# M302D.net
KiCad netlist of a schematic drawn in EAGLE
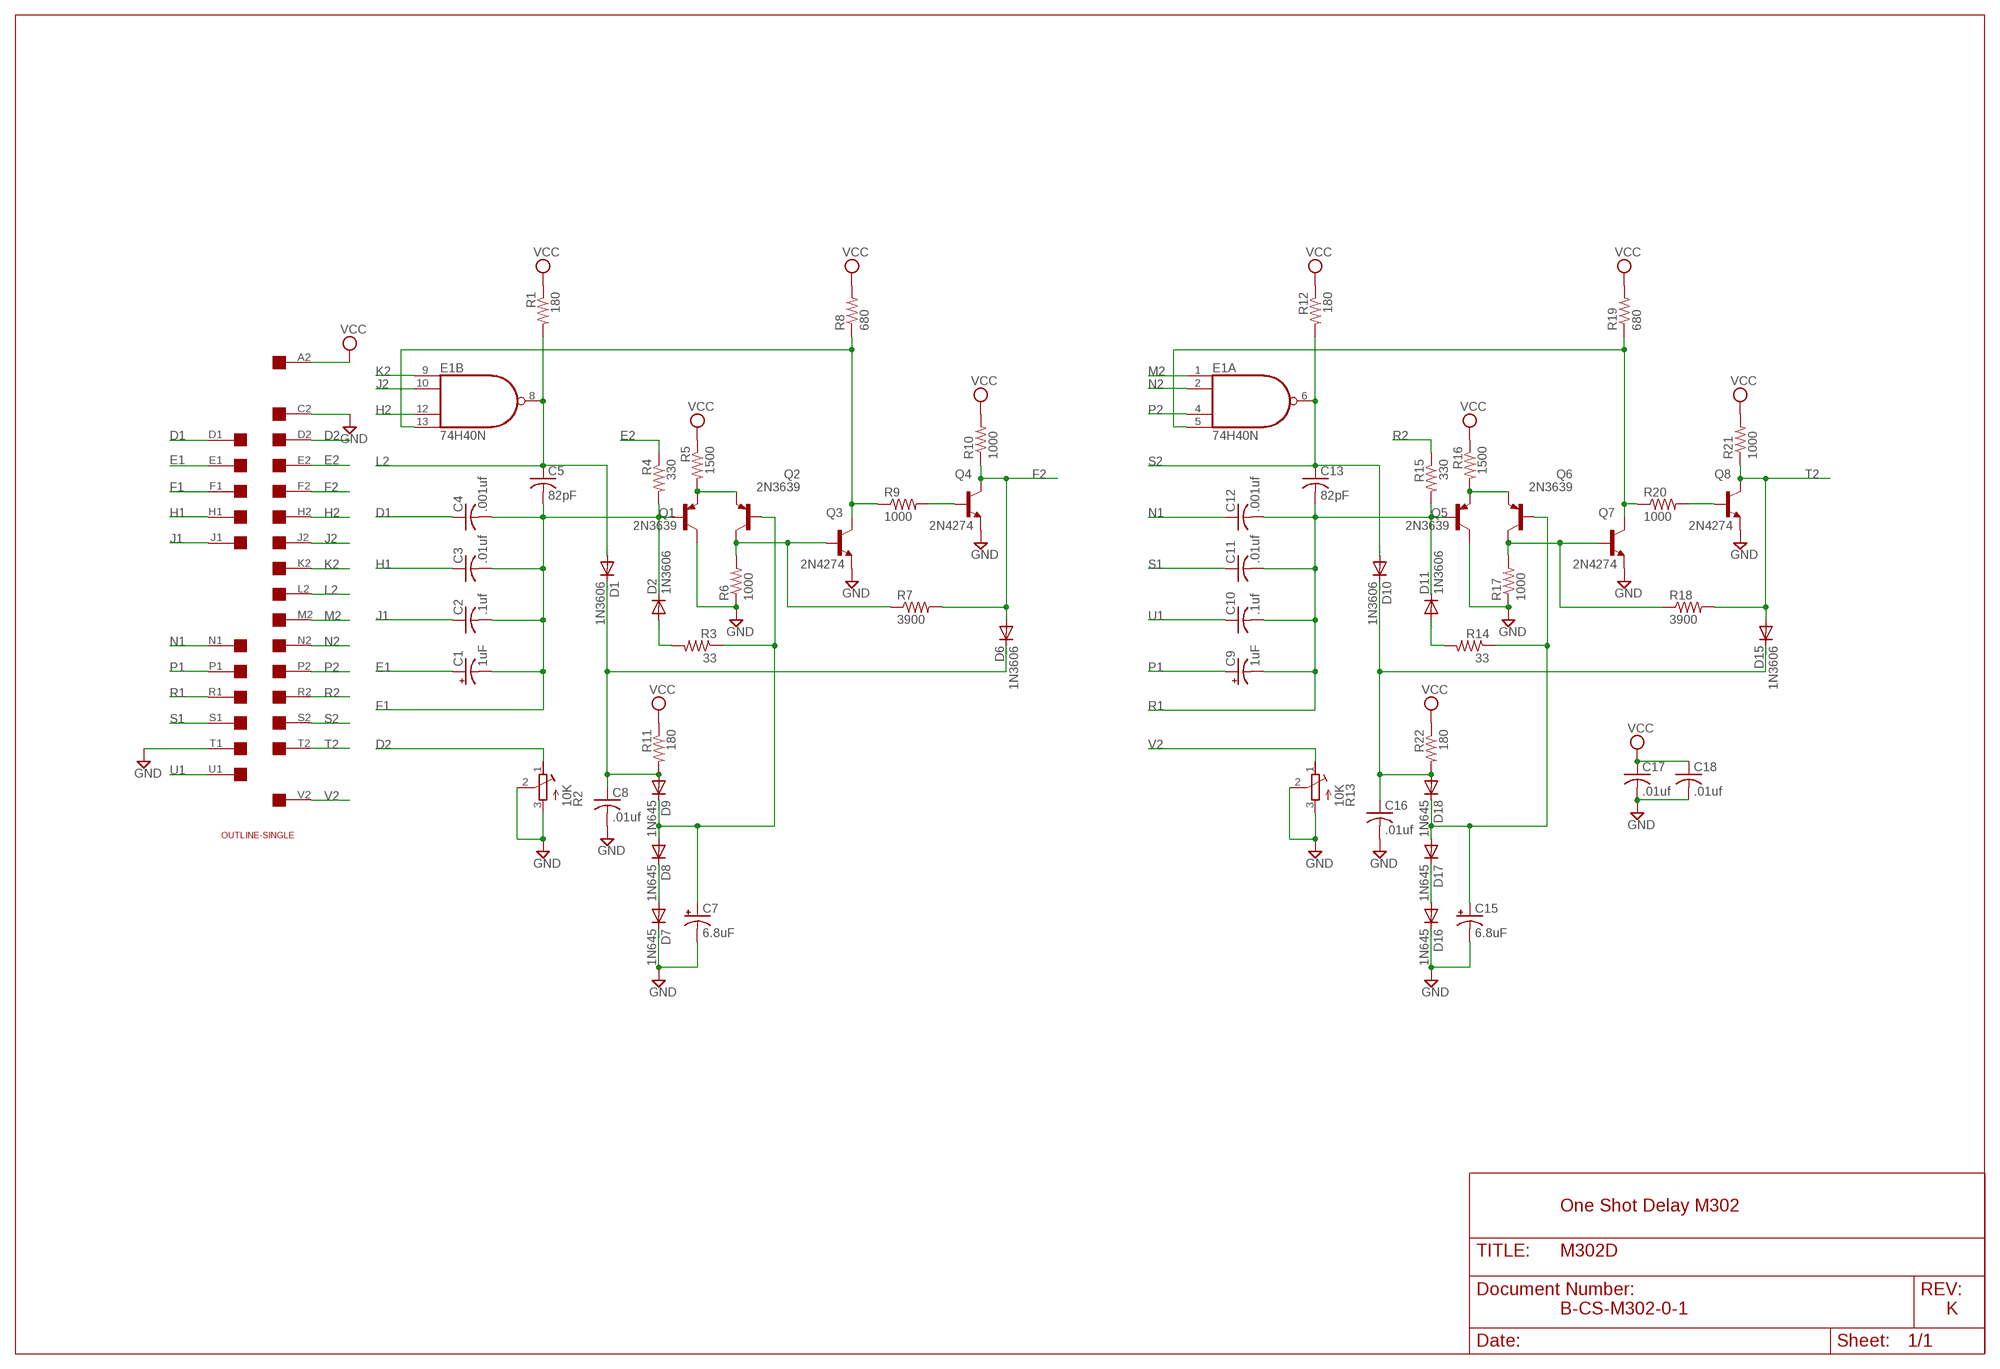
[diagram p0: schematic, sheet 1]

(export (version "E")
  (design (tool "Eeschema 10.0.6"))
  (components
    (comp (ref "C1")
      (value "1uF")
      (footprint "eagle-import:E12-4")
      (libsource (lib "eagle-import") (part "CPOL-USE12-4AXIAL"))
    )
    (comp (ref "C2")
      (value ".1uf")
      (footprint "eagle-import:C275-093X316")
      (libsource (lib "eagle-import") (part "C-US275-093X316"))
    )
    (comp (ref "C3")
      (value ".01uf")
      (footprint "eagle-import:C225-062X268")
      (libsource (lib "eagle-import") (part "C-US225-062X268"))
    )
    (comp (ref "C4")
      (value ".001uf")
      (footprint "eagle-import:C150-054X183")
      (libsource (lib "eagle-import") (part "C-US150-054X183"))
    )
    (comp (ref "C5")
      (value "82pF")
      (footprint "eagle-import:C075-032X103")
      (libsource (lib "eagle-import") (part "C-US075-032X103"))
    )
    (comp (ref "C7")
      (value "6.8uF")
      (footprint "eagle-import:E15-5")
      (libsource (lib "eagle-import") (part "CPOL-USE15-5AXIAL"))
    )
    (comp (ref "C8")
      (value ".01uf")
      (footprint "eagle-import:C050-025X075")
      (libsource (lib "eagle-import") (part "C-US050-025X075"))
    )
    (comp (ref "C9")
      (value "1uF")
      (footprint "eagle-import:E12-4")
      (libsource (lib "eagle-import") (part "CPOL-USE12-4AXIAL"))
    )
    (comp (ref "C10")
      (value ".1uf")
      (footprint "eagle-import:C275-093X316")
      (libsource (lib "eagle-import") (part "C-US275-093X316"))
    )
    (comp (ref "C11")
      (value ".01uf")
      (footprint "eagle-import:C225-062X268")
      (libsource (lib "eagle-import") (part "C-US225-062X268"))
    )
    (comp (ref "C12")
      (value ".001uf")
      (footprint "eagle-import:C150-054X183")
      (libsource (lib "eagle-import") (part "C-US150-054X183"))
    )
    (comp (ref "C13")
      (value "82pF")
      (footprint "eagle-import:C075-032X103")
      (libsource (lib "eagle-import") (part "C-US075-032X103"))
    )
    (comp (ref "C15")
      (value "6.8uF")
      (footprint "eagle-import:E15-5")
      (libsource (lib "eagle-import") (part "CPOL-USE15-5AXIAL"))
    )
    (comp (ref "C16")
      (value ".01uf")
      (footprint "eagle-import:C050-025X075")
      (libsource (lib "eagle-import") (part "C-US050-025X075"))
    )
    (comp (ref "C17")
      (value ".01uf")
      (footprint "eagle-import:C050-025X075")
      (libsource (lib "eagle-import") (part "C-US050-025X075"))
    )
    (comp (ref "C18")
      (value ".01uf")
      (footprint "eagle-import:C050-025X075")
      (libsource (lib "eagle-import") (part "C-US050-025X075"))
    )
    (comp (ref "D1")
      (value "1N3606")
      (footprint "eagle-import:DO35-10")
      (libsource (lib "eagle-import") (part "1N4148DO35-10"))
    )
    (comp (ref "D2")
      (value "1N3606")
      (footprint "eagle-import:DO35-10")
      (libsource (lib "eagle-import") (part "1N4148DO35-10"))
    )
    (comp (ref "D6")
      (value "1N3606")
      (footprint "eagle-import:DO35-10")
      (libsource (lib "eagle-import") (part "1N4148DO35-10"))
    )
    (comp (ref "D7")
      (value "1N645")
      (footprint "eagle-import:DO35-10")
      (libsource (lib "eagle-import") (part "1N4148DO35-10"))
    )
    (comp (ref "D8")
      (value "1N645")
      (footprint "eagle-import:DO35-10")
      (libsource (lib "eagle-import") (part "1N4148DO35-10"))
    )
    (comp (ref "D9")
      (value "1N645")
      (footprint "eagle-import:DO35-10")
      (libsource (lib "eagle-import") (part "1N4148DO35-10"))
    )
    (comp (ref "D10")
      (value "1N3606")
      (footprint "eagle-import:DO35-10")
      (libsource (lib "eagle-import") (part "1N4148DO35-10"))
    )
    (comp (ref "D11")
      (value "1N3606")
      (footprint "eagle-import:DO35-10")
      (libsource (lib "eagle-import") (part "1N4148DO35-10"))
    )
    (comp (ref "D15")
      (value "1N3606")
      (footprint "eagle-import:DO35-10")
      (libsource (lib "eagle-import") (part "1N4148DO35-10"))
    )
    (comp (ref "D16")
      (value "1N645")
      (footprint "eagle-import:DO35-10")
      (libsource (lib "eagle-import") (part "1N4148DO35-10"))
    )
    (comp (ref "D17")
      (value "1N645")
      (footprint "eagle-import:DO35-10")
      (libsource (lib "eagle-import") (part "1N4148DO35-10"))
    )
    (comp (ref "D18")
      (value "1N645")
      (footprint "eagle-import:DO35-10")
      (libsource (lib "eagle-import") (part "1N4148DO35-10"))
    )
    (comp (ref "E1")
      (value "74H40N")
      (footprint "eagle-import:DIL14")
      (libsource (lib "eagle-import") (part "7420NS"))
    )
    (comp (ref "Q1")
      (value "2N3639")
      (footprint "eagle-import:TO39")
      (libsource (lib "eagle-import") (part "-PNP-TO39-EBC2N3637"))
    )
    (comp (ref "Q2")
      (value "2N3639")
      (footprint "eagle-import:TO39")
      (libsource (lib "eagle-import") (part "-PNP-TO39-EBC2N3637"))
    )
    (comp (ref "Q3")
      (value "2N4274")
      (footprint "eagle-import:TO39")
      (libsource (lib "eagle-import") (part "-NPN-TO39-EBC2N3019"))
    )
    (comp (ref "Q4")
      (value "2N4274")
      (footprint "eagle-import:TO39")
      (libsource (lib "eagle-import") (part "-NPN-TO39-EBC2N3019"))
    )
    (comp (ref "Q5")
      (value "2N3639")
      (footprint "eagle-import:TO39")
      (libsource (lib "eagle-import") (part "-PNP-TO39-EBC2N3637"))
    )
    (comp (ref "Q6")
      (value "2N3639")
      (footprint "eagle-import:TO39")
      (libsource (lib "eagle-import") (part "-PNP-TO39-EBC2N3637"))
    )
    (comp (ref "Q7")
      (value "2N4274")
      (footprint "eagle-import:TO39")
      (libsource (lib "eagle-import") (part "-NPN-TO39-EBC2N3019"))
    )
    (comp (ref "Q8")
      (value "2N4274")
      (footprint "eagle-import:TO39")
      (libsource (lib "eagle-import") (part "-NPN-TO39-EBC2N3019"))
    )
    (comp (ref "R1")
      (value "180")
      (footprint "eagle-import:0207_10")
      (libsource (lib "eagle-import") (part "R-US_0207/10"))
    )
    (comp (ref "R2")
      (value "10K")
      (footprint "eagle-import:3006Y")
      (libsource (lib "eagle-import") (part "275P"))
    )
    (comp (ref "R3")
      (value "33")
      (footprint "eagle-import:0207_10")
      (libsource (lib "eagle-import") (part "R-US_0207/10"))
    )
    (comp (ref "R4")
      (value "330")
      (footprint "eagle-import:0207_10")
      (libsource (lib "eagle-import") (part "R-US_0207/10"))
    )
    (comp (ref "R5")
      (value "1500")
      (footprint "eagle-import:0207_10")
      (libsource (lib "eagle-import") (part "R-US_0207/10"))
    )
    (comp (ref "R6")
      (value "1000")
      (footprint "eagle-import:0207_10")
      (libsource (lib "eagle-import") (part "R-US_0207/10"))
    )
    (comp (ref "R7")
      (value "3900")
      (footprint "eagle-import:0207_10")
      (libsource (lib "eagle-import") (part "R-US_0207/10"))
    )
    (comp (ref "R8")
      (value "680")
      (footprint "eagle-import:0207_10")
      (libsource (lib "eagle-import") (part "R-US_0207/10"))
    )
    (comp (ref "R9")
      (value "1000")
      (footprint "eagle-import:0207_10")
      (libsource (lib "eagle-import") (part "R-US_0207/10"))
    )
    (comp (ref "R10")
      (value "1000")
      (footprint "eagle-import:0207_10")
      (libsource (lib "eagle-import") (part "R-US_0207/10"))
    )
    (comp (ref "R11")
      (value "180")
      (footprint "eagle-import:0207_10")
      (libsource (lib "eagle-import") (part "R-US_0207/10"))
    )
    (comp (ref "R12")
      (value "180")
      (footprint "eagle-import:0207_10")
      (libsource (lib "eagle-import") (part "R-US_0207/10"))
    )
    (comp (ref "R13")
      (value "10K")
      (footprint "eagle-import:3006Y")
      (libsource (lib "eagle-import") (part "275P"))
    )
    (comp (ref "R14")
      (value "33")
      (footprint "eagle-import:0207_10")
      (libsource (lib "eagle-import") (part "R-US_0207/10"))
    )
    (comp (ref "R15")
      (value "330")
      (footprint "eagle-import:0207_10")
      (libsource (lib "eagle-import") (part "R-US_0207/10"))
    )
    (comp (ref "R16")
      (value "1500")
      (footprint "eagle-import:0207_10")
      (libsource (lib "eagle-import") (part "R-US_0207/10"))
    )
    (comp (ref "R17")
      (value "1000")
      (footprint "eagle-import:0207_10")
      (libsource (lib "eagle-import") (part "R-US_0207/10"))
    )
    (comp (ref "R18")
      (value "3900")
      (footprint "eagle-import:0207_10")
      (libsource (lib "eagle-import") (part "R-US_0207/10"))
    )
    (comp (ref "R19")
      (value "680")
      (footprint "eagle-import:0207_10")
      (libsource (lib "eagle-import") (part "R-US_0207/10"))
    )
    (comp (ref "R20")
      (value "1000")
      (footprint "eagle-import:0207_10")
      (libsource (lib "eagle-import") (part "R-US_0207/10"))
    )
    (comp (ref "R21")
      (value "1000")
      (footprint "eagle-import:0207_10")
      (libsource (lib "eagle-import") (part "R-US_0207/10"))
    )
    (comp (ref "R22")
      (value "180")
      (footprint "eagle-import:0207_10")
      (libsource (lib "eagle-import") (part "R-US_0207/10"))
    )
    (comp (ref "U$1")
      (value "SINGLE")
      (footprint "eagle-import:EDGE-CON2")
      (libsource (lib "eagle-import") (part "SINGLE"))
    )
    (comp (ref "U$2")
      (value "OUTLINE-SINGLE")
      (footprint "eagle-import:SINGLE")
      (libsource (lib "eagle-import") (part "OUTLINE-SINGLE"))
    )
  )
  (nets
    (net (code "1") (name "/D1") (class "Default")
      (node (ref "C4") (pin "1") (pinfunction "1_1") (pintype "passive"))
      (node (ref "U$1") (pin "D1") (pinfunction "1_D1") (pintype "bidirectional"))
    )
    (net (code "2") (name "/D2") (class "Default")
      (node (ref "R2") (pin "1") (pinfunction "A_1") (pintype "passive"))
      (node (ref "U$1") (pin "D2") (pinfunction "1_D2") (pintype "bidirectional"))
    )
    (net (code "3") (name "/E1") (class "Default")
      (node (ref "C1") (pin "+") (pinfunction "+_+") (pintype "passive"))
      (node (ref "U$1") (pin "E1") (pinfunction "1_E1") (pintype "bidirectional"))
    )
    (net (code "4") (name "/E2") (class "Default")
      (node (ref "R4") (pin "1") (pinfunction "1_1") (pintype "passive"))
      (node (ref "U$1") (pin "E2") (pinfunction "1_E2") (pintype "bidirectional"))
    )
    (net (code "5") (name "/F1") (class "Default")
      (node (ref "C1") (pin "-") (pinfunction "-_-") (pintype "passive"))
      (node (ref "C2") (pin "2") (pinfunction "2_2") (pintype "passive"))
      (node (ref "C3") (pin "2") (pinfunction "2_2") (pintype "passive"))
      (node (ref "C4") (pin "2") (pinfunction "2_2") (pintype "passive"))
      (node (ref "C5") (pin "2") (pinfunction "2_2") (pintype "passive"))
      (node (ref "D2") (pin "C") (pinfunction "C_C") (pintype "passive"))
      (node (ref "Q1") (pin "2") (pinfunction "B_2") (pintype "passive"))
      (node (ref "R4") (pin "2") (pinfunction "2_2") (pintype "passive"))
      (node (ref "U$1") (pin "F1") (pinfunction "1_F1") (pintype "bidirectional"))
    )
    (net (code "6") (name "/F2") (class "Default")
      (node (ref "D6") (pin "A") (pinfunction "A_A") (pintype "passive"))
      (node (ref "Q4") (pin "3") (pinfunction "C_3") (pintype "passive"))
      (node (ref "R10") (pin "1") (pinfunction "1_1") (pintype "passive"))
      (node (ref "R7") (pin "2") (pinfunction "2_2") (pintype "passive"))
      (node (ref "U$1") (pin "F2") (pinfunction "1_F2") (pintype "bidirectional"))
    )
    (net (code "7") (name "/H1") (class "Default")
      (node (ref "C3") (pin "1") (pinfunction "1_1") (pintype "passive"))
      (node (ref "U$1") (pin "H1") (pinfunction "1_H1") (pintype "bidirectional"))
    )
    (net (code "8") (name "/H2") (class "Default")
      (node (ref "E1") (pin "12") (pinfunction "I2_12") (pintype "input"))
      (node (ref "U$1") (pin "H2") (pinfunction "1_H2") (pintype "bidirectional"))
    )
    (net (code "9") (name "/J1") (class "Default")
      (node (ref "C2") (pin "1") (pinfunction "1_1") (pintype "passive"))
      (node (ref "U$1") (pin "J1") (pinfunction "1_J1") (pintype "bidirectional"))
    )
    (net (code "10") (name "/J2") (class "Default")
      (node (ref "E1") (pin "10") (pinfunction "I1_10") (pintype "input"))
      (node (ref "U$1") (pin "J2") (pinfunction "1_J2") (pintype "bidirectional"))
    )
    (net (code "11") (name "/K2") (class "Default")
      (node (ref "E1") (pin "9") (pinfunction "I0_9") (pintype "input"))
      (node (ref "U$1") (pin "K2") (pinfunction "1_K2") (pintype "bidirectional"))
    )
    (net (code "12") (name "/L2") (class "Default")
      (node (ref "C5") (pin "1") (pinfunction "1_1") (pintype "passive"))
      (node (ref "D1") (pin "A") (pinfunction "A_A") (pintype "passive"))
      (node (ref "E1") (pin "8") (pinfunction "O_8") (pintype "output"))
      (node (ref "R1") (pin "2") (pinfunction "2_2") (pintype "passive"))
      (node (ref "U$1") (pin "L2") (pinfunction "1_L2") (pintype "bidirectional"))
    )
    (net (code "13") (name "/M2") (class "Default")
      (node (ref "E1") (pin "1") (pinfunction "I0_1") (pintype "input"))
      (node (ref "U$1") (pin "M2") (pinfunction "1_M2") (pintype "bidirectional"))
    )
    (net (code "14") (name "/N1") (class "Default")
      (node (ref "C12") (pin "1") (pinfunction "1_1") (pintype "passive"))
      (node (ref "U$1") (pin "N1") (pinfunction "1_N1") (pintype "bidirectional"))
    )
    (net (code "15") (name "/N2") (class "Default")
      (node (ref "E1") (pin "2") (pinfunction "I1_2") (pintype "input"))
      (node (ref "U$1") (pin "N2") (pinfunction "1_N2") (pintype "bidirectional"))
    )
    (net (code "16") (name "/P1") (class "Default")
      (node (ref "C9") (pin "+") (pinfunction "+_+") (pintype "passive"))
      (node (ref "U$1") (pin "P1") (pinfunction "1_P1") (pintype "bidirectional"))
    )
    (net (code "17") (name "/P2") (class "Default")
      (node (ref "E1") (pin "4") (pinfunction "I2_4") (pintype "input"))
      (node (ref "U$1") (pin "P2") (pinfunction "1_P2") (pintype "bidirectional"))
    )
    (net (code "18") (name "/R1") (class "Default")
      (node (ref "C10") (pin "2") (pinfunction "2_2") (pintype "passive"))
      (node (ref "C11") (pin "2") (pinfunction "2_2") (pintype "passive"))
      (node (ref "C12") (pin "2") (pinfunction "2_2") (pintype "passive"))
      (node (ref "C13") (pin "2") (pinfunction "2_2") (pintype "passive"))
      (node (ref "C9") (pin "-") (pinfunction "-_-") (pintype "passive"))
      (node (ref "D11") (pin "C") (pinfunction "C_C") (pintype "passive"))
      (node (ref "Q5") (pin "2") (pinfunction "B_2") (pintype "passive"))
      (node (ref "R15") (pin "2") (pinfunction "2_2") (pintype "passive"))
      (node (ref "U$1") (pin "R1") (pinfunction "1_R1") (pintype "bidirectional"))
    )
    (net (code "19") (name "/R2") (class "Default")
      (node (ref "R15") (pin "1") (pinfunction "1_1") (pintype "passive"))
      (node (ref "U$1") (pin "R2") (pinfunction "1_R2") (pintype "bidirectional"))
    )
    (net (code "20") (name "/S1") (class "Default")
      (node (ref "C11") (pin "1") (pinfunction "1_1") (pintype "passive"))
      (node (ref "U$1") (pin "S1") (pinfunction "1_S1") (pintype "bidirectional"))
    )
    (net (code "21") (name "/S2") (class "Default")
      (node (ref "C13") (pin "1") (pinfunction "1_1") (pintype "passive"))
      (node (ref "D10") (pin "A") (pinfunction "A_A") (pintype "passive"))
      (node (ref "E1") (pin "6") (pinfunction "O_6") (pintype "output"))
      (node (ref "R12") (pin "2") (pinfunction "2_2") (pintype "passive"))
      (node (ref "U$1") (pin "S2") (pinfunction "1_S2") (pintype "bidirectional"))
    )
    (net (code "22") (name "/T2") (class "Default")
      (node (ref "D15") (pin "A") (pinfunction "A_A") (pintype "passive"))
      (node (ref "Q8") (pin "3") (pinfunction "C_3") (pintype "passive"))
      (node (ref "R18") (pin "2") (pinfunction "2_2") (pintype "passive"))
      (node (ref "R21") (pin "1") (pinfunction "1_1") (pintype "passive"))
      (node (ref "U$1") (pin "T2") (pinfunction "1_T2") (pintype "bidirectional"))
    )
    (net (code "23") (name "/U1") (class "Default")
      (node (ref "C10") (pin "1") (pinfunction "1_1") (pintype "passive"))
      (node (ref "U$1") (pin "U1") (pinfunction "1_U1") (pintype "bidirectional"))
    )
    (net (code "24") (name "/V2") (class "Default")
      (node (ref "R13") (pin "1") (pinfunction "A_1") (pintype "passive"))
      (node (ref "U$1") (pin "V2") (pinfunction "1_V2") (pintype "bidirectional"))
    )
    (net (code "25") (name "GND") (class "Default")
      (node (ref "C15") (pin "-") (pinfunction "-_-") (pintype "passive"))
      (node (ref "C16") (pin "2") (pinfunction "2_2") (pintype "passive"))
      (node (ref "C17") (pin "2") (pinfunction "2_2") (pintype "passive"))
      (node (ref "C18") (pin "2") (pinfunction "2_2") (pintype "passive"))
      (node (ref "C7") (pin "-") (pinfunction "-_-") (pintype "passive"))
      (node (ref "C8") (pin "2") (pinfunction "2_2") (pintype "passive"))
      (node (ref "D16") (pin "C") (pinfunction "C_C") (pintype "passive"))
      (node (ref "D7") (pin "C") (pinfunction "C_C") (pintype "passive"))
      (node (ref "Q1") (pin "3") (pinfunction "C_3") (pintype "passive"))
      (node (ref "Q3") (pin "1") (pinfunction "E_1") (pintype "passive"))
      (node (ref "Q4") (pin "1") (pinfunction "E_1") (pintype "passive"))
      (node (ref "Q5") (pin "3") (pinfunction "C_3") (pintype "passive"))
      (node (ref "Q7") (pin "1") (pinfunction "E_1") (pintype "passive"))
      (node (ref "Q8") (pin "1") (pinfunction "E_1") (pintype "passive"))
      (node (ref "R13") (pin "2") (pinfunction "S_2") (pintype "passive"))
      (node (ref "R13") (pin "3") (pinfunction "E_3") (pintype "passive"))
      (node (ref "R17") (pin "1") (pinfunction "1_1") (pintype "passive"))
      (node (ref "R2") (pin "2") (pinfunction "S_2") (pintype "passive"))
      (node (ref "R2") (pin "3") (pinfunction "E_3") (pintype "passive"))
      (node (ref "R6") (pin "1") (pinfunction "1_1") (pintype "passive"))
      (node (ref "U$1") (pin "C2") (pinfunction "1_C2") (pintype "bidirectional"))
      (node (ref "U$1") (pin "T1") (pinfunction "1_T1") (pintype "bidirectional"))
    )
    (net (code "26") (name "Net-(C8-Pad1)") (class "Default")
      (node (ref "C8") (pin "1") (pinfunction "1_1") (pintype "passive"))
      (node (ref "D1") (pin "C") (pinfunction "C_C") (pintype "passive"))
      (node (ref "D6") (pin "C") (pinfunction "C_C") (pintype "passive"))
      (node (ref "D9") (pin "A") (pinfunction "A_A") (pintype "passive"))
      (node (ref "R11") (pin "2") (pinfunction "2_2") (pintype "passive"))
    )
    (net (code "27") (name "Net-(C16-Pad1)") (class "Default")
      (node (ref "C16") (pin "1") (pinfunction "1_1") (pintype "passive"))
      (node (ref "D10") (pin "C") (pinfunction "C_C") (pintype "passive"))
      (node (ref "D15") (pin "C") (pinfunction "C_C") (pintype "passive"))
      (node (ref "D18") (pin "A") (pinfunction "A_A") (pintype "passive"))
      (node (ref "R22") (pin "2") (pinfunction "2_2") (pintype "passive"))
    )
    (net (code "28") (name "Net-(D2-PadA)") (class "Default")
      (node (ref "D2") (pin "A") (pinfunction "A_A") (pintype "passive"))
      (node (ref "R3") (pin "2") (pinfunction "2_2") (pintype "passive"))
    )
    (net (code "29") (name "Net-(D7-PadA)") (class "Default")
      (node (ref "D7") (pin "A") (pinfunction "A_A") (pintype "passive"))
      (node (ref "D8") (pin "C") (pinfunction "C_C") (pintype "passive"))
    )
    (net (code "30") (name "Net-(D11-PadA)") (class "Default")
      (node (ref "D11") (pin "A") (pinfunction "A_A") (pintype "passive"))
      (node (ref "R14") (pin "2") (pinfunction "2_2") (pintype "passive"))
    )
    (net (code "31") (name "Net-(D16-PadA)") (class "Default")
      (node (ref "D16") (pin "A") (pinfunction "A_A") (pintype "passive"))
      (node (ref "D17") (pin "C") (pinfunction "C_C") (pintype "passive"))
    )
    (net (code "32") (name "Net-(E1A-I3)") (class "Default")
      (node (ref "E1") (pin "5") (pinfunction "I3_5") (pintype "input"))
      (node (ref "Q7") (pin "3") (pinfunction "C_3") (pintype "passive"))
      (node (ref "R19") (pin "1") (pinfunction "1_1") (pintype "passive"))
      (node (ref "R20") (pin "1") (pinfunction "1_1") (pintype "passive"))
    )
    (net (code "33") (name "Net-(E1B-I3)") (class "Default")
      (node (ref "E1") (pin "13") (pinfunction "I3_13") (pintype "input"))
      (node (ref "Q3") (pin "3") (pinfunction "C_3") (pintype "passive"))
      (node (ref "R8") (pin "1") (pinfunction "1_1") (pintype "passive"))
      (node (ref "R9") (pin "1") (pinfunction "1_1") (pintype "passive"))
    )
    (net (code "34") (name "Net-(Q1-E)") (class "Default")
      (node (ref "Q1") (pin "1") (pinfunction "E_1") (pintype "passive"))
      (node (ref "Q2") (pin "1") (pinfunction "E_1") (pintype "passive"))
      (node (ref "R5") (pin "2") (pinfunction "2_2") (pintype "passive"))
    )
    (net (code "35") (name "Net-(Q2-B)") (class "Default")
      (node (ref "C7") (pin "+") (pinfunction "+_+") (pintype "passive"))
      (node (ref "D8") (pin "A") (pinfunction "A_A") (pintype "passive"))
      (node (ref "D9") (pin "C") (pinfunction "C_C") (pintype "passive"))
      (node (ref "Q2") (pin "2") (pinfunction "B_2") (pintype "passive"))
      (node (ref "R3") (pin "1") (pinfunction "1_1") (pintype "passive"))
    )
    (net (code "36") (name "Net-(Q2-C)") (class "Default")
      (node (ref "Q2") (pin "3") (pinfunction "C_3") (pintype "passive"))
      (node (ref "Q3") (pin "2") (pinfunction "B_2") (pintype "passive"))
      (node (ref "R6") (pin "2") (pinfunction "2_2") (pintype "passive"))
      (node (ref "R7") (pin "1") (pinfunction "1_1") (pintype "passive"))
    )
    (net (code "37") (name "Net-(Q4-B)") (class "Default")
      (node (ref "Q4") (pin "2") (pinfunction "B_2") (pintype "passive"))
      (node (ref "R9") (pin "2") (pinfunction "2_2") (pintype "passive"))
    )
    (net (code "38") (name "Net-(Q5-E)") (class "Default")
      (node (ref "Q5") (pin "1") (pinfunction "E_1") (pintype "passive"))
      (node (ref "Q6") (pin "1") (pinfunction "E_1") (pintype "passive"))
      (node (ref "R16") (pin "2") (pinfunction "2_2") (pintype "passive"))
    )
    (net (code "39") (name "Net-(Q6-B)") (class "Default")
      (node (ref "C15") (pin "+") (pinfunction "+_+") (pintype "passive"))
      (node (ref "D17") (pin "A") (pinfunction "A_A") (pintype "passive"))
      (node (ref "D18") (pin "C") (pinfunction "C_C") (pintype "passive"))
      (node (ref "Q6") (pin "2") (pinfunction "B_2") (pintype "passive"))
      (node (ref "R14") (pin "1") (pinfunction "1_1") (pintype "passive"))
    )
    (net (code "40") (name "Net-(Q6-C)") (class "Default")
      (node (ref "Q6") (pin "3") (pinfunction "C_3") (pintype "passive"))
      (node (ref "Q7") (pin "2") (pinfunction "B_2") (pintype "passive"))
      (node (ref "R17") (pin "2") (pinfunction "2_2") (pintype "passive"))
      (node (ref "R18") (pin "1") (pinfunction "1_1") (pintype "passive"))
    )
    (net (code "41") (name "Net-(Q8-B)") (class "Default")
      (node (ref "Q8") (pin "2") (pinfunction "B_2") (pintype "passive"))
      (node (ref "R20") (pin "2") (pinfunction "2_2") (pintype "passive"))
    )
    (net (code "42") (name "VCC") (class "Default")
      (node (ref "C17") (pin "1") (pinfunction "1_1") (pintype "passive"))
      (node (ref "C18") (pin "1") (pinfunction "1_1") (pintype "passive"))
      (node (ref "R1") (pin "1") (pinfunction "1_1") (pintype "passive"))
      (node (ref "R10") (pin "2") (pinfunction "2_2") (pintype "passive"))
      (node (ref "R11") (pin "1") (pinfunction "1_1") (pintype "passive"))
      (node (ref "R12") (pin "1") (pinfunction "1_1") (pintype "passive"))
      (node (ref "R16") (pin "1") (pinfunction "1_1") (pintype "passive"))
      (node (ref "R19") (pin "2") (pinfunction "2_2") (pintype "passive"))
      (node (ref "R21") (pin "2") (pinfunction "2_2") (pintype "passive"))
      (node (ref "R22") (pin "1") (pinfunction "1_1") (pintype "passive"))
      (node (ref "R5") (pin "1") (pinfunction "1_1") (pintype "passive"))
      (node (ref "R8") (pin "2") (pinfunction "2_2") (pintype "passive"))
      (node (ref "U$1") (pin "A2") (pinfunction "1_A2") (pintype "bidirectional"))
    )
  )
)
